# Sheet1.net
KiCad netlist of a schematic drawn in Altium Designer
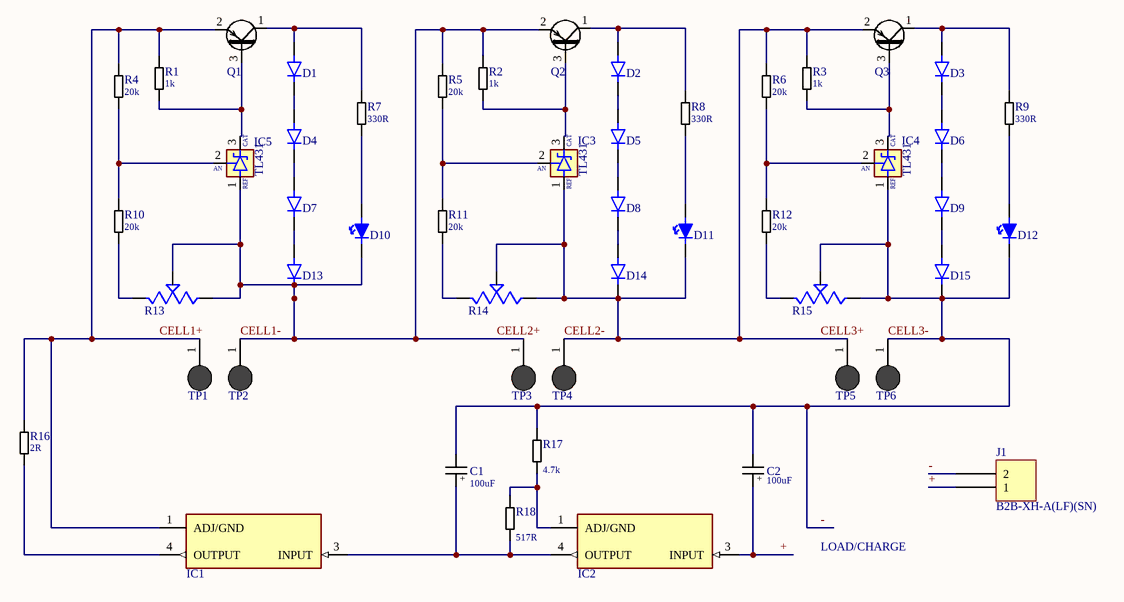
[diagram p0: Sheet1.SchDoc]

(export (version "E")
  (design (tool "Eeschema 10.0.6"))
  (components
    (comp (ref "C1")
      (value "493-15610-ND")
      (footprint "AL_ELEC_CAP_RAD")
      (description "Cap Aluminum Lytic 100uF 16V 20% (6.3 X 11mm) Radial 2.5mm 175mA 2000h 105 Bulk")
      (fields
        (field (name "MANUFACTURER") "Nichicon")
        (field (name "MANUFACTURER PART NUMBER") "UPJ1C101MED")
        (field (name "CAPACITANCE") "100uF")
        (field (name "DESIGNED BY") "Semih AŞÇI")
      )
      (libsource (lib "Integrated_Library1") (part "CAP 100uF Radial TH"))
    )
    (comp (ref "C2")
      (value "493-15610-ND")
      (footprint "AL_ELEC_CAP_RAD")
      (description "Cap Aluminum Lytic 100uF 16V 20% (6.3 X 11mm) Radial 2.5mm 175mA 2000h 105 Bulk")
      (fields
        (field (name "MANUFACTURER") "Nichicon")
        (field (name "MANUFACTURER PART NUMBER") "UPJ1C101MED")
        (field (name "CAPACITANCE") "100uF")
        (field (name "DESIGNED BY") "Semih AŞÇI")
      )
      (libsource (lib "Integrated_Library1") (part "CAP 100uF Radial TH"))
    )
    (comp (ref "D1")
      (value "1N4007 SMD")
      (footprint "DO-214AC")
      (description "VR=1000V IF=1A 15pF")
      (fields
        (field (name "MANUFACTURER") "ON Semiconductor / Fairchild")
        (field (name "MANUFACTURER PART NUMBER") "1N4007")
      )
      (libsource (lib "Integrated_Library1") (part "1N4007 SMD"))
    )
    (comp (ref "D2")
      (value "1N4007 SMD")
      (footprint "DO-214AC")
      (description "VR=1000V IF=1A 15pF")
      (fields
        (field (name "MANUFACTURER") "ON Semiconductor / Fairchild")
        (field (name "MANUFACTURER PART NUMBER") "1N4007")
      )
      (libsource (lib "Integrated_Library1") (part "1N4007 SMD"))
    )
    (comp (ref "D3")
      (value "1N4007 SMD")
      (footprint "DO-214AC")
      (description "VR=1000V IF=1A 15pF")
      (fields
        (field (name "MANUFACTURER") "ON Semiconductor / Fairchild")
        (field (name "MANUFACTURER PART NUMBER") "1N4007")
      )
      (libsource (lib "Integrated_Library1") (part "1N4007 SMD"))
    )
    (comp (ref "D4")
      (value "1N4007 SMD")
      (footprint "DO-214AC")
      (description "VR=1000V IF=1A 15pF")
      (fields
        (field (name "MANUFACTURER") "ON Semiconductor / Fairchild")
        (field (name "MANUFACTURER PART NUMBER") "1N4007")
      )
      (libsource (lib "Integrated_Library1") (part "1N4007 SMD"))
    )
    (comp (ref "D5")
      (value "1N4007 SMD")
      (footprint "DO-214AC")
      (description "VR=1000V IF=1A 15pF")
      (fields
        (field (name "MANUFACTURER") "ON Semiconductor / Fairchild")
        (field (name "MANUFACTURER PART NUMBER") "1N4007")
      )
      (libsource (lib "Integrated_Library1") (part "1N4007 SMD"))
    )
    (comp (ref "D6")
      (value "1N4007 SMD")
      (footprint "DO-214AC")
      (description "VR=1000V IF=1A 15pF")
      (fields
        (field (name "MANUFACTURER") "ON Semiconductor / Fairchild")
        (field (name "MANUFACTURER PART NUMBER") "1N4007")
      )
      (libsource (lib "Integrated_Library1") (part "1N4007 SMD"))
    )
    (comp (ref "D7")
      (value "1N4007 SMD")
      (footprint "DO-214AC")
      (description "VR=1000V IF=1A 15pF")
      (fields
        (field (name "MANUFACTURER") "ON Semiconductor / Fairchild")
        (field (name "MANUFACTURER PART NUMBER") "1N4007")
      )
      (libsource (lib "Integrated_Library1") (part "1N4007 SMD"))
    )
    (comp (ref "D8")
      (value "1N4007 SMD")
      (footprint "DO-214AC")
      (description "VR=1000V IF=1A 15pF")
      (fields
        (field (name "MANUFACTURER") "ON Semiconductor / Fairchild")
        (field (name "MANUFACTURER PART NUMBER") "1N4007")
      )
      (libsource (lib "Integrated_Library1") (part "1N4007 SMD"))
    )
    (comp (ref "D9")
      (value "1N4007 SMD")
      (footprint "DO-214AC")
      (description "VR=1000V IF=1A 15pF")
      (fields
        (field (name "MANUFACTURER") "ON Semiconductor / Fairchild")
        (field (name "MANUFACTURER PART NUMBER") "1N4007")
      )
      (libsource (lib "Integrated_Library1") (part "1N4007 SMD"))
    )
    (comp (ref "D10")
      (value "LED TH")
      (footprint "TH_LED")
      (description "Radial red led")
      (fields (field (name "DESIGNED BY") "Semih AŞÇI"))
      (libsource (lib "Integrated_Library1") (part "LED TH"))
    )
    (comp (ref "D11")
      (value "LED TH")
      (footprint "TH_LED")
      (description "Radial red led")
      (fields (field (name "DESIGNED BY") "Semih AŞÇI"))
      (libsource (lib "Integrated_Library1") (part "LED TH"))
    )
    (comp (ref "D12")
      (value "LED TH")
      (footprint "TH_LED")
      (description "Radial red led")
      (fields (field (name "DESIGNED BY") "Semih AŞÇI"))
      (libsource (lib "Integrated_Library1") (part "LED TH"))
    )
    (comp (ref "D13")
      (value "1N4007 SMD")
      (footprint "DO-214AC")
      (description "VR=1000V IF=1A 15pF")
      (fields
        (field (name "MANUFACTURER") "ON Semiconductor / Fairchild")
        (field (name "MANUFACTURER PART NUMBER") "1N4007")
      )
      (libsource (lib "Integrated_Library1") (part "1N4007 SMD"))
    )
    (comp (ref "D14")
      (value "1N4007 SMD")
      (footprint "DO-214AC")
      (description "VR=1000V IF=1A 15pF")
      (fields
        (field (name "MANUFACTURER") "ON Semiconductor / Fairchild")
        (field (name "MANUFACTURER PART NUMBER") "1N4007")
      )
      (libsource (lib "Integrated_Library1") (part "1N4007 SMD"))
    )
    (comp (ref "D15")
      (value "1N4007 SMD")
      (footprint "DO-214AC")
      (description "VR=1000V IF=1A 15pF")
      (fields
        (field (name "MANUFACTURER") "ON Semiconductor / Fairchild")
        (field (name "MANUFACTURER PART NUMBER") "1N4007")
      )
      (libsource (lib "Integrated_Library1") (part "1N4007 SMD"))
    )
    (comp (ref "IC1")
      (value "497-1574-2-ND")
      (footprint "TO-252-3")
      (description "Reg Standard Lin Adj Pos 1.2V to 37V 0.2A 3-Pin (2+Tab) DPAK T/R")
      (fields
        (field (name "MANUFACTURER") "STMicroelectronics")
        (field (name "MANUFACTURER PART NUMBER") "LM317MDT-TR")
      )
      (libsource (lib "Integrated_Library1") (part "LM317"))
    )
    (comp (ref "IC2")
      (value "497-1574-2-ND")
      (footprint "TO-252-3")
      (description "Reg Standard Lin Adj Pos 1.2V to 37V 0.2A 3-Pin (2+Tab) DPAK T/R")
      (fields
        (field (name "MANUFACTURER") "STMicroelectronics")
        (field (name "MANUFACTURER PART NUMBER") "LM317MDT-TR")
      )
      (libsource (lib "Integrated_Library1") (part "LM317"))
    )
    (comp (ref "IC3")
      (value "TL431")
      (footprint "TO92-3")
      (libsource (lib "Integrated_Library1") (part "TL431"))
    )
    (comp (ref "IC4")
      (value "TL431")
      (footprint "TO92-3")
      (libsource (lib "Integrated_Library1") (part "TL431"))
    )
    (comp (ref "IC5")
      (value "TL431")
      (footprint "TO92-3")
      (libsource (lib "Integrated_Library1") (part "TL431"))
    )
    (comp (ref "J1")
      (value "B2B-XH-A(LF)(SN)")
      (footprint "JST XH B2B-XH-A")
      (description "CONN HEADER VERT 2POS 2.5MM")
      (fields (field (name "MANUFACTURER") "JST Sales America Inc."))
      (libsource (lib "Celestial Altium Library - altium_library") (part "2 Pin"))
    )
    (comp (ref "Q1")
      (value "BD140")
      (footprint "TO126 (SOT32)")
      (description "Trans GP BJT PNP 80V 1.5A 1250mW 3-Pin(3+Tab) SOT-32 Tube / TRANS PNP 80V 1.5A SOT-32")
      (fields
        (field (name "MANUFACTURER") "ON Semiconductor / Fairchild")
        (field (name "DESIGNED BY") "Semih AŞÇI")
      )
      (libsource (lib "Integrated_Library1") (part "BD140"))
    )
    (comp (ref "Q2")
      (value "BD140")
      (footprint "TO126 (SOT32)")
      (description "Trans GP BJT PNP 80V 1.5A 1250mW 3-Pin(3+Tab) SOT-32 Tube / TRANS PNP 80V 1.5A SOT-32")
      (fields
        (field (name "MANUFACTURER") "ON Semiconductor / Fairchild")
        (field (name "DESIGNED BY") "Semih AŞÇI")
      )
      (libsource (lib "Integrated_Library1") (part "BD140"))
    )
    (comp (ref "Q3")
      (value "BD140")
      (footprint "TO126 (SOT32)")
      (description "Trans GP BJT PNP 80V 1.5A 1250mW 3-Pin(3+Tab) SOT-32 Tube / TRANS PNP 80V 1.5A SOT-32")
      (fields
        (field (name "MANUFACTURER") "ON Semiconductor / Fairchild")
        (field (name "DESIGNED BY") "Semih AŞÇI")
      )
      (libsource (lib "Integrated_Library1") (part "BD140"))
    )
    (comp (ref "R1")
      (value "RES 1K OHM TH")
      (footprint "TH_RES")
      (description "Res 1k Ohm TH")
      (fields (field (name "RESISTANCE") "1k") (field (name "DESIGNED BY") "Semih AŞÇI"))
      (libsource (lib "Integrated_Library1") (part "RES 1K OHM TH"))
    )
    (comp (ref "R2")
      (value "RES 1K OHM TH")
      (footprint "TH_RES")
      (description "Res 1k Ohm TH")
      (fields (field (name "RESISTANCE") "1k") (field (name "DESIGNED BY") "Semih AŞÇI"))
      (libsource (lib "Integrated_Library1") (part "RES 1K OHM TH"))
    )
    (comp (ref "R3")
      (value "RES 1K OHM TH")
      (footprint "TH_RES")
      (description "Res 1k Ohm TH")
      (fields (field (name "RESISTANCE") "1k") (field (name "DESIGNED BY") "Semih AŞÇI"))
      (libsource (lib "Integrated_Library1") (part "RES 1K OHM TH"))
    )
    (comp (ref "R4")
      (value "RES 20K OHM TH")
      (footprint "TH_RES")
      (description "Res 20K Ohm  TH")
      (fields (field (name "RESISTANCE") "20k") (field (name "DESIGNED BY") "Semih AŞÇI"))
      (libsource (lib "Integrated_Library1") (part "RES 20K OHM TH"))
    )
    (comp (ref "R5")
      (value "RES 20K OHM TH")
      (footprint "TH_RES")
      (description "Res 20K Ohm  TH")
      (fields (field (name "RESISTANCE") "20k") (field (name "DESIGNED BY") "Semih AŞÇI"))
      (libsource (lib "Integrated_Library1") (part "RES 20K OHM TH"))
    )
    (comp (ref "R6")
      (value "RES 20K OHM TH")
      (footprint "TH_RES")
      (description "Res 20K Ohm  TH")
      (fields (field (name "RESISTANCE") "20k") (field (name "DESIGNED BY") "Semih AŞÇI"))
      (libsource (lib "Integrated_Library1") (part "RES 20K OHM TH"))
    )
    (comp (ref "R7")
      (value "RES 330R OHM TH")
      (footprint "TH_RES")
      (description "Res 330R Ohm  TH")
      (fields (field (name "RESISTANCE") "330R") (field (name "DESIGNED BY") "Semih AŞÇI"))
      (libsource (lib "Integrated_Library1") (part "RES 330R OHM TH"))
    )
    (comp (ref "R8")
      (value "RES 330R OHM TH")
      (footprint "TH_RES")
      (description "Res 330R Ohm  TH")
      (fields (field (name "RESISTANCE") "330R") (field (name "DESIGNED BY") "Semih AŞÇI"))
      (libsource (lib "Integrated_Library1") (part "RES 330R OHM TH"))
    )
    (comp (ref "R9")
      (value "RES 330R OHM TH")
      (footprint "TH_RES")
      (description "Res 330R Ohm  TH")
      (fields (field (name "RESISTANCE") "330R") (field (name "DESIGNED BY") "Semih AŞÇI"))
      (libsource (lib "Integrated_Library1") (part "RES 330R OHM TH"))
    )
    (comp (ref "R10")
      (value "RES 20K OHM TH")
      (footprint "TH_RES")
      (description "Res 20K Ohm  TH")
      (fields (field (name "RESISTANCE") "20k") (field (name "DESIGNED BY") "Semih AŞÇI"))
      (libsource (lib "Integrated_Library1") (part "RES 20K OHM TH"))
    )
    (comp (ref "R11")
      (value "RES 20K OHM TH")
      (footprint "TH_RES")
      (description "Res 20K Ohm  TH")
      (fields (field (name "RESISTANCE") "20k") (field (name "DESIGNED BY") "Semih AŞÇI"))
      (libsource (lib "Integrated_Library1") (part "RES 20K OHM TH"))
    )
    (comp (ref "R12")
      (value "RES 20K OHM TH")
      (footprint "TH_RES")
      (description "Res 20K Ohm  TH")
      (fields (field (name "RESISTANCE") "20k") (field (name "DESIGNED BY") "Semih AŞÇI"))
      (libsource (lib "Integrated_Library1") (part "RES 20K OHM TH"))
    )
    (comp (ref "R13")
      (value "TRIMPOT")
      (footprint "Trimpot_tube")
      (description "20k trimpot")
      (fields (field (name "DESIGNED BY") "Semih AŞÇI"))
      (libsource (lib "Integrated_Library1") (part "TRIMPOT"))
    )
    (comp (ref "R14")
      (value "TRIMPOT")
      (footprint "Trimpot_tube")
      (description "20k trimpot")
      (fields (field (name "DESIGNED BY") "Semih AŞÇI"))
      (libsource (lib "Integrated_Library1") (part "TRIMPOT"))
    )
    (comp (ref "R15")
      (value "TRIMPOT")
      (footprint "Trimpot_tube")
      (description "20k trimpot")
      (fields (field (name "DESIGNED BY") "Semih AŞÇI"))
      (libsource (lib "Integrated_Library1") (part "TRIMPOT"))
    )
    (comp (ref "R16")
      (value "RES 2R OHM TH")
      (footprint "TH_RES")
      (description "Res 2R Ohm 1W TH")
      (fields (field (name "RESISTANCE") "2R") (field (name "DESIGNED BY") "Semih AŞÇI"))
      (libsource (lib "Integrated_Library1") (part "RES 2R OHM TH"))
    )
    (comp (ref "R17")
      (value "RES 4.7K OHM TH")
      (footprint "TH_RES")
      (description "Res 4.7K Ohm  TH")
      (fields (field (name "RESISTANCE") "4.7k") (field (name "DESIGNED BY") "Semih AŞÇI"))
      (libsource (lib "Integrated_Library1") (part "RES 4.7K OHM TH"))
    )
    (comp (ref "R18")
      (value "RES 517R OHM TH")
      (footprint "TH_RES")
      (description "Res 517R Ohm  TH")
      (fields (field (name "RESISTANCE") "517R") (field (name "DESIGNED BY") "Semih AŞÇI"))
      (libsource (lib "Integrated_Library1") (part "RES 517R OHM TH"))
    )
    (comp (ref "TP1")
      (value "TEST PAD")
      (footprint "TEST_PAD")
      (libsource (lib "Integrated_Library1") (part "TEST PAD"))
    )
    (comp (ref "TP2")
      (value "TEST PAD")
      (footprint "TEST_PAD")
      (libsource (lib "Integrated_Library1") (part "TEST PAD"))
    )
    (comp (ref "TP3")
      (value "TEST PAD")
      (footprint "TEST_PAD")
      (libsource (lib "Integrated_Library1") (part "TEST PAD"))
    )
    (comp (ref "TP4")
      (value "TEST PAD")
      (footprint "TEST_PAD")
      (libsource (lib "Integrated_Library1") (part "TEST PAD"))
    )
    (comp (ref "TP5")
      (value "TEST PAD")
      (footprint "TEST_PAD")
      (libsource (lib "Integrated_Library1") (part "TEST PAD"))
    )
    (comp (ref "TP6")
      (value "TEST PAD")
      (footprint "TEST_PAD")
      (libsource (lib "Integrated_Library1") (part "TEST PAD"))
    )
  )
  (nets
    (net (code "1") (name "/+") (class "Default")
      (node (ref "C2") (pin "1") (pinfunction "1_1") (pintype "passive"))
      (node (ref "IC2") (pin "3") (pinfunction "INPUT_3") (pintype "input"))
      (node (ref "J1") (pin "1") (pinfunction "1_1") (pintype "passive"))
    )
    (net (code "2") (name "/-") (class "Default")
      (node (ref "C1") (pin "2") (pinfunction "2_2") (pintype "passive"))
      (node (ref "C2") (pin "2") (pinfunction "2_2") (pintype "passive"))
      (node (ref "D12") (pin "1") (pinfunction "1_1") (pintype "passive"))
      (node (ref "D15") (pin "C") (pinfunction "K_C") (pintype "passive"))
      (node (ref "IC4") (pin "1") (pinfunction "REF_1") (pintype "passive"))
      (node (ref "J1") (pin "2") (pinfunction "2_2") (pintype "passive"))
      (node (ref "R15") (pin "1") (pinfunction "CCW_1") (pintype "passive"))
      (node (ref "R15") (pin "2") (pinfunction "WIPER_2") (pintype "passive"))
      (node (ref "R17") (pin "2") (pinfunction "2_2") (pintype "passive"))
      (node (ref "TP6") (pin "1") (pinfunction "1_1") (pintype "passive"))
    )
    (net (code "3") (name "/CELL1+") (class "Default")
      (node (ref "IC1") (pin "1") (pinfunction "ADJ/GND_1") (pintype "power_in"))
      (node (ref "Q1") (pin "2") (pinfunction "C_2") (pintype "passive"))
      (node (ref "R1") (pin "2") (pinfunction "2_2") (pintype "passive"))
      (node (ref "R16") (pin "2") (pinfunction "2_2") (pintype "passive"))
      (node (ref "R4") (pin "2") (pinfunction "2_2") (pintype "passive"))
      (node (ref "TP1") (pin "1") (pinfunction "1_1") (pintype "passive"))
    )
    (net (code "4") (name "/CELL1-") (class "Default")
      (node (ref "D10") (pin "1") (pinfunction "1_1") (pintype "passive"))
      (node (ref "D13") (pin "C") (pinfunction "K_C") (pintype "passive"))
      (node (ref "IC5") (pin "1") (pinfunction "REF_1") (pintype "passive"))
      (node (ref "Q2") (pin "2") (pinfunction "C_2") (pintype "passive"))
      (node (ref "R13") (pin "1") (pinfunction "CCW_1") (pintype "passive"))
      (node (ref "R13") (pin "2") (pinfunction "WIPER_2") (pintype "passive"))
      (node (ref "R2") (pin "2") (pinfunction "2_2") (pintype "passive"))
      (node (ref "R5") (pin "2") (pinfunction "2_2") (pintype "passive"))
      (node (ref "TP2") (pin "1") (pinfunction "1_1") (pintype "passive"))
      (node (ref "TP3") (pin "1") (pinfunction "1_1") (pintype "passive"))
    )
    (net (code "5") (name "/CELL2-") (class "Default")
      (node (ref "D11") (pin "1") (pinfunction "1_1") (pintype "passive"))
      (node (ref "D14") (pin "C") (pinfunction "K_C") (pintype "passive"))
      (node (ref "IC3") (pin "1") (pinfunction "REF_1") (pintype "passive"))
      (node (ref "Q3") (pin "2") (pinfunction "C_2") (pintype "passive"))
      (node (ref "R14") (pin "1") (pinfunction "CCW_1") (pintype "passive"))
      (node (ref "R14") (pin "2") (pinfunction "WIPER_2") (pintype "passive"))
      (node (ref "R3") (pin "2") (pinfunction "2_2") (pintype "passive"))
      (node (ref "R6") (pin "2") (pinfunction "2_2") (pintype "passive"))
      (node (ref "TP4") (pin "1") (pinfunction "1_1") (pintype "passive"))
      (node (ref "TP5") (pin "1") (pinfunction "1_1") (pintype "passive"))
    )
    (net (code "6") (name "Net-(D1-K)") (class "Default")
      (node (ref "D1") (pin "C") (pinfunction "K_C") (pintype "passive"))
      (node (ref "D4") (pin "A") (pinfunction "A_A") (pintype "passive"))
    )
    (net (code "7") (name "Net-(D2-K)") (class "Default")
      (node (ref "D2") (pin "C") (pinfunction "K_C") (pintype "passive"))
      (node (ref "D5") (pin "A") (pinfunction "A_A") (pintype "passive"))
    )
    (net (code "8") (name "Net-(D3-K)") (class "Default")
      (node (ref "D3") (pin "C") (pinfunction "K_C") (pintype "passive"))
      (node (ref "D6") (pin "A") (pinfunction "A_A") (pintype "passive"))
    )
    (net (code "9") (name "Net-(D4-K)") (class "Default")
      (node (ref "D4") (pin "C") (pinfunction "K_C") (pintype "passive"))
      (node (ref "D7") (pin "A") (pinfunction "A_A") (pintype "passive"))
    )
    (net (code "10") (name "Net-(D5-K)") (class "Default")
      (node (ref "D5") (pin "C") (pinfunction "K_C") (pintype "passive"))
      (node (ref "D8") (pin "A") (pinfunction "A_A") (pintype "passive"))
    )
    (net (code "11") (name "Net-(D6-K)") (class "Default")
      (node (ref "D6") (pin "C") (pinfunction "K_C") (pintype "passive"))
      (node (ref "D9") (pin "A") (pinfunction "A_A") (pintype "passive"))
    )
    (net (code "12") (name "Net-(D7-K)") (class "Default")
      (node (ref "D13") (pin "A") (pinfunction "A_A") (pintype "passive"))
      (node (ref "D7") (pin "C") (pinfunction "K_C") (pintype "passive"))
    )
    (net (code "13") (name "Net-(D8-K)") (class "Default")
      (node (ref "D14") (pin "A") (pinfunction "A_A") (pintype "passive"))
      (node (ref "D8") (pin "C") (pinfunction "K_C") (pintype "passive"))
    )
    (net (code "14") (name "Net-(D9-K)") (class "Default")
      (node (ref "D15") (pin "A") (pinfunction "A_A") (pintype "passive"))
      (node (ref "D9") (pin "C") (pinfunction "K_C") (pintype "passive"))
    )
    (net (code "15") (name "Net-(D10-Pad2)") (class "Default")
      (node (ref "D10") (pin "2") (pinfunction "2_2") (pintype "passive"))
      (node (ref "R7") (pin "1") (pinfunction "1_1") (pintype "passive"))
    )
    (net (code "16") (name "Net-(D11-Pad2)") (class "Default")
      (node (ref "D11") (pin "2") (pinfunction "2_2") (pintype "passive"))
      (node (ref "R8") (pin "1") (pinfunction "1_1") (pintype "passive"))
    )
    (net (code "17") (name "Net-(D12-Pad2)") (class "Default")
      (node (ref "D12") (pin "2") (pinfunction "2_2") (pintype "passive"))
      (node (ref "R9") (pin "1") (pinfunction "1_1") (pintype "passive"))
    )
    (net (code "18") (name "Net-(IC1-INPUT)") (class "Default")
      (node (ref "C1") (pin "1") (pinfunction "1_1") (pintype "passive"))
      (node (ref "IC1") (pin "3") (pinfunction "INPUT_3") (pintype "input"))
      (node (ref "IC2") (pin "4") (pinfunction "OUTPUT_4") (pintype "output"))
      (node (ref "R18") (pin "1") (pinfunction "1_1") (pintype "passive"))
    )
    (net (code "19") (name "Net-(IC1-OUTPUT)") (class "Default")
      (node (ref "IC1") (pin "4") (pinfunction "OUTPUT_4") (pintype "output"))
      (node (ref "R16") (pin "1") (pinfunction "1_1") (pintype "passive"))
    )
    (net (code "20") (name "Net-(IC2-ADJ{slash}GND)") (class "Default")
      (node (ref "IC2") (pin "1") (pinfunction "ADJ/GND_1") (pintype "power_in"))
      (node (ref "R17") (pin "1") (pinfunction "1_1") (pintype "passive"))
      (node (ref "R18") (pin "2") (pinfunction "2_2") (pintype "passive"))
    )
    (net (code "21") (name "Net-(IC3-ANODE)") (class "Default")
      (node (ref "IC3") (pin "2") (pinfunction "ANODE_2") (pintype "passive"))
      (node (ref "R11") (pin "2") (pinfunction "2_2") (pintype "passive"))
      (node (ref "R5") (pin "1") (pinfunction "1_1") (pintype "passive"))
    )
    (net (code "22") (name "Net-(IC3-CATHODE)") (class "Default")
      (node (ref "IC3") (pin "3") (pinfunction "CATHODE_3") (pintype "passive"))
      (node (ref "Q2") (pin "3") (pinfunction "B_3") (pintype "passive"))
      (node (ref "R2") (pin "1") (pinfunction "1_1") (pintype "passive"))
    )
    (net (code "23") (name "Net-(IC4-ANODE)") (class "Default")
      (node (ref "IC4") (pin "2") (pinfunction "ANODE_2") (pintype "passive"))
      (node (ref "R12") (pin "2") (pinfunction "2_2") (pintype "passive"))
      (node (ref "R6") (pin "1") (pinfunction "1_1") (pintype "passive"))
    )
    (net (code "24") (name "Net-(IC4-CATHODE)") (class "Default")
      (node (ref "IC4") (pin "3") (pinfunction "CATHODE_3") (pintype "passive"))
      (node (ref "Q3") (pin "3") (pinfunction "B_3") (pintype "passive"))
      (node (ref "R3") (pin "1") (pinfunction "1_1") (pintype "passive"))
    )
    (net (code "25") (name "Net-(IC5-ANODE)") (class "Default")
      (node (ref "IC5") (pin "2") (pinfunction "ANODE_2") (pintype "passive"))
      (node (ref "R10") (pin "2") (pinfunction "2_2") (pintype "passive"))
      (node (ref "R4") (pin "1") (pinfunction "1_1") (pintype "passive"))
    )
    (net (code "26") (name "Net-(IC5-CATHODE)") (class "Default")
      (node (ref "IC5") (pin "3") (pinfunction "CATHODE_3") (pintype "passive"))
      (node (ref "Q1") (pin "3") (pinfunction "B_3") (pintype "passive"))
      (node (ref "R1") (pin "1") (pinfunction "1_1") (pintype "passive"))
    )
    (net (code "27") (name "Net-(Q1-E)") (class "Default")
      (node (ref "D1") (pin "A") (pinfunction "A_A") (pintype "passive"))
      (node (ref "Q1") (pin "1") (pinfunction "E_1") (pintype "passive"))
      (node (ref "R7") (pin "2") (pinfunction "2_2") (pintype "passive"))
    )
    (net (code "28") (name "Net-(Q2-E)") (class "Default")
      (node (ref "D2") (pin "A") (pinfunction "A_A") (pintype "passive"))
      (node (ref "Q2") (pin "1") (pinfunction "E_1") (pintype "passive"))
      (node (ref "R8") (pin "2") (pinfunction "2_2") (pintype "passive"))
    )
    (net (code "29") (name "Net-(Q3-E)") (class "Default")
      (node (ref "D3") (pin "A") (pinfunction "A_A") (pintype "passive"))
      (node (ref "Q3") (pin "1") (pinfunction "E_1") (pintype "passive"))
      (node (ref "R9") (pin "2") (pinfunction "2_2") (pintype "passive"))
    )
    (net (code "30") (name "Net-(R13-CW)") (class "Default")
      (node (ref "R10") (pin "1") (pinfunction "1_1") (pintype "passive"))
      (node (ref "R13") (pin "3") (pinfunction "CW_3") (pintype "passive"))
    )
    (net (code "31") (name "Net-(R14-CW)") (class "Default")
      (node (ref "R11") (pin "1") (pinfunction "1_1") (pintype "passive"))
      (node (ref "R14") (pin "3") (pinfunction "CW_3") (pintype "passive"))
    )
    (net (code "32") (name "Net-(R15-CW)") (class "Default")
      (node (ref "R12") (pin "1") (pinfunction "1_1") (pintype "passive"))
      (node (ref "R15") (pin "3") (pinfunction "CW_3") (pintype "passive"))
    )
  )
)
